# Main.net
KiCad netlist of a schematic drawn in Altium Designer
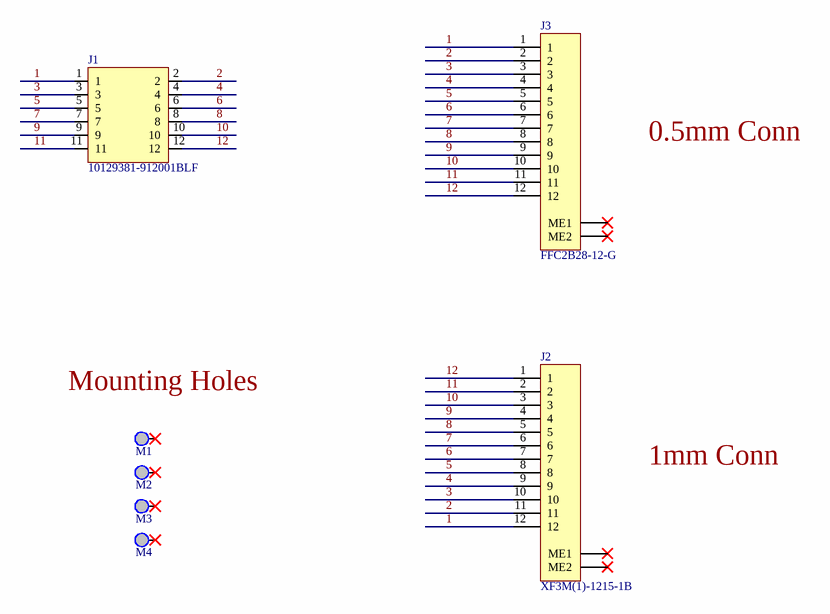
[diagram p0: Main.SchDoc]

(export (version "E")
  (design (tool "Eeschema 10.0.6"))
  (components
    (comp (ref "J1")
      (value "10129381-912001BLF")
      (footprint "HDR-V-2X6-2.54MM")
      (description "Conn Unshrouded Header HDR 12 POS 2.54mm Solder ST Thru-Hole Poly Bag")
      (libsource (lib "intercreate") (part "HDR-V-2X6-M-2.54MM"))
    )
    (comp (ref "J2")
      (value "XF3M(1)-1215-1B")
      (footprint "CONN-FFC-H-12P-1MM")
      (description "FFC & FPC Connectors RotaryBackLock 1.0mm Dual Contact 12pin")
      (libsource (lib "intercreate") (part "CONN-FFC-H-12P-1MM"))
    )
    (comp (ref "J3")
      (value "FFC2B28-12-G")
      (footprint "CONN-FFC-H-12P-0.5MM")
      (libsource (lib "intercreate") (part "CONN-FFC-H-12P-0.5MM"))
    )
    (comp (ref "M1")
      (value "MTG_HOLE")
      (footprint "MH_P_2.5MM")
      (description "MTG HOLE PLATED VARIOUS SIZES")
      (libsource (lib "intercreate") (part "MTG_HOLE"))
    )
    (comp (ref "M2")
      (value "MTG_HOLE")
      (footprint "MH_P_2.5MM")
      (description "MTG HOLE PLATED VARIOUS SIZES")
      (libsource (lib "intercreate") (part "MTG_HOLE"))
    )
    (comp (ref "M3")
      (value "MTG_HOLE")
      (footprint "MH_P_2.5MM")
      (description "MTG HOLE PLATED VARIOUS SIZES")
      (libsource (lib "intercreate") (part "MTG_HOLE"))
    )
    (comp (ref "M4")
      (value "MTG_HOLE")
      (footprint "MH_P_2.5MM")
      (description "MTG HOLE PLATED VARIOUS SIZES")
      (libsource (lib "intercreate") (part "MTG_HOLE"))
    )
  )
  (nets
    (net (code "1") (name "/1") (class "Default")
      (node (ref "J1") (pin "1") (pinfunction "1_1") (pintype "passive"))
      (node (ref "J2") (pin "12") (pinfunction "12_12") (pintype "passive"))
      (node (ref "J3") (pin "1") (pinfunction "1_1") (pintype "passive"))
    )
    (net (code "2") (name "/2") (class "Default")
      (node (ref "J1") (pin "2") (pinfunction "2_2") (pintype "passive"))
      (node (ref "J2") (pin "11") (pinfunction "11_11") (pintype "passive"))
      (node (ref "J3") (pin "2") (pinfunction "2_2") (pintype "passive"))
    )
    (net (code "3") (name "/3") (class "Default")
      (node (ref "J1") (pin "3") (pinfunction "3_3") (pintype "passive"))
      (node (ref "J2") (pin "10") (pinfunction "10_10") (pintype "passive"))
      (node (ref "J3") (pin "3") (pinfunction "3_3") (pintype "passive"))
    )
    (net (code "4") (name "/4") (class "Default")
      (node (ref "J1") (pin "4") (pinfunction "4_4") (pintype "passive"))
      (node (ref "J2") (pin "9") (pinfunction "9_9") (pintype "passive"))
      (node (ref "J3") (pin "4") (pinfunction "4_4") (pintype "passive"))
    )
    (net (code "5") (name "/5") (class "Default")
      (node (ref "J1") (pin "5") (pinfunction "5_5") (pintype "passive"))
      (node (ref "J2") (pin "8") (pinfunction "8_8") (pintype "passive"))
      (node (ref "J3") (pin "5") (pinfunction "5_5") (pintype "passive"))
    )
    (net (code "6") (name "/6") (class "Default")
      (node (ref "J1") (pin "6") (pinfunction "6_6") (pintype "passive"))
      (node (ref "J2") (pin "7") (pinfunction "7_7") (pintype "passive"))
      (node (ref "J3") (pin "6") (pinfunction "6_6") (pintype "passive"))
    )
    (net (code "7") (name "/7") (class "Default")
      (node (ref "J1") (pin "7") (pinfunction "7_7") (pintype "passive"))
      (node (ref "J2") (pin "6") (pinfunction "6_6") (pintype "passive"))
      (node (ref "J3") (pin "7") (pinfunction "7_7") (pintype "passive"))
    )
    (net (code "8") (name "/8") (class "Default")
      (node (ref "J1") (pin "8") (pinfunction "8_8") (pintype "passive"))
      (node (ref "J2") (pin "5") (pinfunction "5_5") (pintype "passive"))
      (node (ref "J3") (pin "8") (pinfunction "8_8") (pintype "passive"))
    )
    (net (code "9") (name "/9") (class "Default")
      (node (ref "J1") (pin "9") (pinfunction "9_9") (pintype "passive"))
      (node (ref "J2") (pin "4") (pinfunction "4_4") (pintype "passive"))
      (node (ref "J3") (pin "9") (pinfunction "9_9") (pintype "passive"))
    )
    (net (code "10") (name "/10") (class "Default")
      (node (ref "J1") (pin "10") (pinfunction "10_10") (pintype "passive"))
      (node (ref "J2") (pin "3") (pinfunction "3_3") (pintype "passive"))
      (node (ref "J3") (pin "10") (pinfunction "10_10") (pintype "passive"))
    )
    (net (code "11") (name "/11") (class "Default")
      (node (ref "J1") (pin "11") (pinfunction "11_11") (pintype "passive"))
      (node (ref "J2") (pin "2") (pinfunction "2_2") (pintype "passive"))
      (node (ref "J3") (pin "11") (pinfunction "11_11") (pintype "passive"))
    )
    (net (code "12") (name "/12") (class "Default")
      (node (ref "J1") (pin "12") (pinfunction "12_12") (pintype "passive"))
      (node (ref "J2") (pin "1") (pinfunction "1_1") (pintype "passive"))
      (node (ref "J3") (pin "12") (pinfunction "12_12") (pintype "passive"))
    )
    (net (code "13") (name "unconnected-(J2-PadME1)") (class "Default")
      (node (ref "J2") (pin "ME1") (pinfunction "ME1_ME1") (pintype "passive+no_connect"))
    )
    (net (code "14") (name "unconnected-(J2-PadME2)") (class "Default")
      (node (ref "J2") (pin "ME2") (pinfunction "ME2_ME2") (pintype "passive+no_connect"))
    )
    (net (code "15") (name "unconnected-(J3-PadME1)") (class "Default")
      (node (ref "J3") (pin "ME1") (pinfunction "ME1_ME1") (pintype "passive+no_connect"))
    )
    (net (code "16") (name "unconnected-(J3-PadME2)") (class "Default")
      (node (ref "J3") (pin "ME2") (pinfunction "ME2_ME2") (pintype "passive+no_connect"))
    )
    (net (code "17") (name "unconnected-(M1-Pad1)") (class "Default")
      (node (ref "M1") (pin "1") (pinfunction "1_1") (pintype "passive+no_connect"))
    )
    (net (code "18") (name "unconnected-(M2-Pad1)") (class "Default")
      (node (ref "M2") (pin "1") (pinfunction "1_1") (pintype "passive+no_connect"))
    )
    (net (code "19") (name "unconnected-(M3-Pad1)") (class "Default")
      (node (ref "M3") (pin "1") (pinfunction "1_1") (pintype "passive+no_connect"))
    )
    (net (code "20") (name "unconnected-(M4-Pad1)") (class "Default")
      (node (ref "M4") (pin "1") (pinfunction "1_1") (pintype "passive+no_connect"))
    )
  )
)
